# VestibularH1.net
KiCad netlist of a schematic drawn in EAGLE
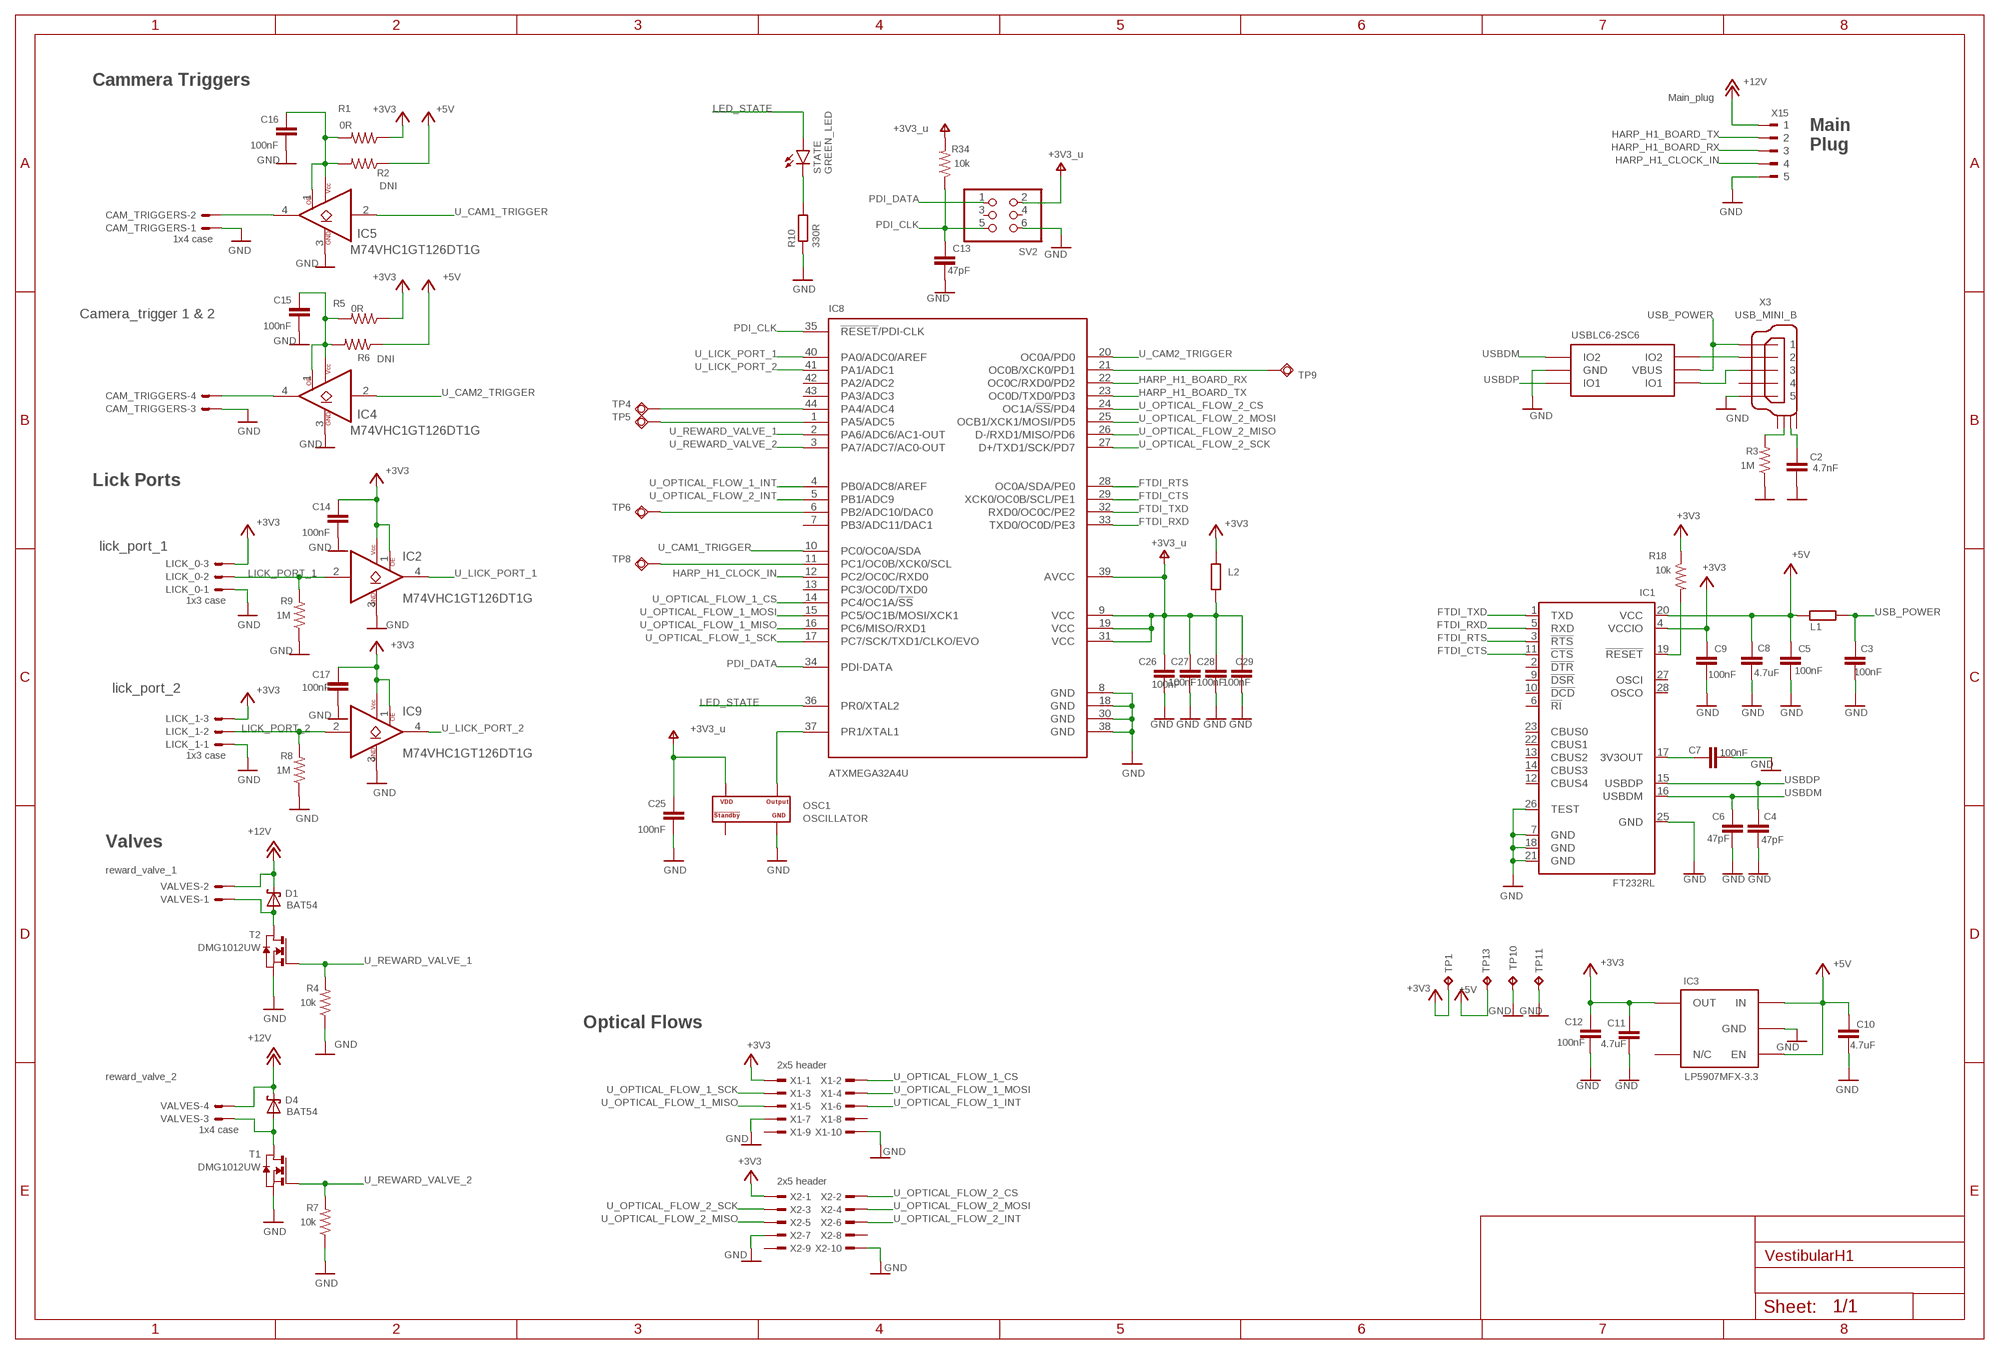
[diagram p0: schematic, sheet 1]

(export (version "E")
  (design (tool "Eeschema 10.0.6"))
  (components
    (comp (ref "C2")
      (value "4.7nF")
      (footprint "eagle-import:C0402K")
      (fields (field (name "MPN") "CC0402KRX7R8BB472"))
      (libsource (lib "eagle-import") (part "C-EUC0402K"))
    )
    (comp (ref "C3")
      (value "100nF")
      (footprint "eagle-import:C0402K")
      (fields (field (name "MPN") "C1005X7R1H104K050BB"))
      (libsource (lib "eagle-import") (part "C-EUC0402K"))
    )
    (comp (ref "C4")
      (value "47pF")
      (footprint "eagle-import:C0402K")
      (fields (field (name "MPN") "04025A470JAT2A"))
      (libsource (lib "eagle-import") (part "C-EUC0402K"))
    )
    (comp (ref "C5")
      (value "100nF")
      (footprint "eagle-import:C0402K")
      (fields (field (name "MPN") "C1005X7R1H104K050BB"))
      (libsource (lib "eagle-import") (part "C-EUC0402K"))
    )
    (comp (ref "C6")
      (value "47pF")
      (footprint "eagle-import:C0402K")
      (fields (field (name "MPN") "04025A470JAT2A"))
      (libsource (lib "eagle-import") (part "C-EUC0402K"))
    )
    (comp (ref "C7")
      (value "100nF")
      (footprint "eagle-import:C0402K")
      (fields (field (name "MPN") "C1005X7R1H104K050BB"))
      (libsource (lib "eagle-import") (part "C-EUC0402K"))
    )
    (comp (ref "C8")
      (value "4.7uF")
      (footprint "eagle-import:C0603")
      (fields (field (name "MPN") "C1608X6S1C475K080AC"))
      (libsource (lib "eagle-import") (part "C-EUC0603"))
    )
    (comp (ref "C9")
      (value "100nF")
      (footprint "eagle-import:C0402K")
      (fields (field (name "MPN") "C1005X7R1H104K050BB"))
      (libsource (lib "eagle-import") (part "C-EUC0402K"))
    )
    (comp (ref "C10")
      (value "4.7uF")
      (footprint "eagle-import:C0603")
      (fields (field (name "MPN") "C1608X6S1C475K080AC"))
      (libsource (lib "eagle-import") (part "C-EUC0603"))
    )
    (comp (ref "C11")
      (value "4.7uF")
      (footprint "eagle-import:C0603K")
      (fields (field (name "MPN") "C1608X6S1C475K080AC"))
      (libsource (lib "eagle-import") (part "C-EUC0603K"))
    )
    (comp (ref "C12")
      (value "100nF")
      (footprint "eagle-import:C0402K")
      (fields (field (name "MPN") "C1005X7R1H104K050BB"))
      (libsource (lib "eagle-import") (part "C-EUC0402K"))
    )
    (comp (ref "C13")
      (value "47pF")
      (footprint "eagle-import:C0402K")
      (fields (field (name "MPN") "04025A470JAT2A"))
      (libsource (lib "eagle-import") (part "C-EUC0402K"))
    )
    (comp (ref "C14")
      (value "100nF")
      (footprint "eagle-import:C0402K")
      (fields (field (name "MPN") "C1005X7R1H104K050BB"))
      (libsource (lib "eagle-import") (part "C-EUC0402K"))
    )
    (comp (ref "C15")
      (value "100nF")
      (footprint "eagle-import:C0402K")
      (fields (field (name "MPN") "C1005X7R1H104K050BB"))
      (libsource (lib "eagle-import") (part "C-EUC0402K"))
    )
    (comp (ref "C16")
      (value "100nF")
      (footprint "eagle-import:C0402K")
      (fields (field (name "MPN") "C1005X7R1H104K050BB"))
      (libsource (lib "eagle-import") (part "C-EUC0402K"))
    )
    (comp (ref "C17")
      (value "100nF")
      (footprint "eagle-import:C0402K")
      (fields (field (name "MPN") "C1005X7R1H104K050BB"))
      (libsource (lib "eagle-import") (part "C-EUC0402K"))
    )
    (comp (ref "C25")
      (value "100nF")
      (footprint "eagle-import:C0402K")
      (fields (field (name "MPN") "C1005X7R1H104K050BB"))
      (libsource (lib "eagle-import") (part "C-EUC0402K"))
    )
    (comp (ref "C26")
      (value "100nF")
      (footprint "eagle-import:C0402K")
      (fields (field (name "MPN") "C1005X7R1H104K050BB"))
      (libsource (lib "eagle-import") (part "C-EUC0402K"))
    )
    (comp (ref "C27")
      (value "100nF")
      (footprint "eagle-import:C0402K")
      (fields (field (name "MPN") "C1005X7R1H104K050BB"))
      (libsource (lib "eagle-import") (part "C-EUC0402K"))
    )
    (comp (ref "C28")
      (value "100nF")
      (footprint "eagle-import:C0402K")
      (fields (field (name "MPN") "C1005X7R1H104K050BB"))
      (libsource (lib "eagle-import") (part "C-EUC0402K"))
    )
    (comp (ref "C29")
      (value "100nF")
      (footprint "eagle-import:C0402K")
      (fields (field (name "MPN") "C1005X7R1H104K050BB"))
      (libsource (lib "eagle-import") (part "C-EUC0402K"))
    )
    (comp (ref "CAM_TRIGGERS")
      (value "1x4 case")
      (footprint "eagle-import:22-23-2041")
      (fields
        (field (name "MF") "MOLEX")
        (field (name "MPN") "22-23-2041")
        (field (name "MF_1") "-")
        (field (name "MPN_1") "282834-4")
        (field (name "OEPS") "OEPS070036")
      )
      (libsource (lib "eagle-import") (part "22-23-2041"))
    )
    (comp (ref "D1")
      (value "BAT54")
      (footprint "eagle-import:SOT23")
      (fields (field (name "MPN") "BAT54SLT1G"))
      (libsource (lib "eagle-import") (part "BAT54"))
    )
    (comp (ref "D4")
      (value "BAT54")
      (footprint "eagle-import:SOT23")
      (fields (field (name "MPN") "BAT54SLT1G"))
      (libsource (lib "eagle-import") (part "BAT54"))
    )
    (comp (ref "IC1")
      (value "FT232RL")
      (footprint "eagle-import:SSOP28")
      (libsource (lib "eagle-import") (part "FT232RL"))
    )
    (comp (ref "IC2")
      (value "M74VHC1GT126DT1G")
      (footprint "eagle-import:TSOP-5")
      (libsource (lib "eagle-import") (part "M74VHC1GT126DT1G"))
    )
    (comp (ref "IC3")
      (value "LP5907MFX-3.3")
      (footprint "eagle-import:TSOT23-5")
      (fields (field (name "MPN") "LP5907MFX-3.3/NOPB"))
      (libsource (lib "eagle-import") (part "TLV700XX"))
    )
    (comp (ref "IC4")
      (value "M74VHC1GT126DT1G")
      (footprint "eagle-import:TSOP-5")
      (libsource (lib "eagle-import") (part "M74VHC1GT126DT1G"))
    )
    (comp (ref "IC5")
      (value "M74VHC1GT126DT1G")
      (footprint "eagle-import:TSOP-5")
      (libsource (lib "eagle-import") (part "M74VHC1GT126DT1G"))
    )
    (comp (ref "IC7")
      (value "USBLC6-2SC6")
      (footprint "eagle-import:SOT23-6L")
      (libsource (lib "eagle-import") (part "USBLC6-2SC6"))
    )
    (comp (ref "IC8")
      (value "ATXMEGA32A4U")
      (footprint "eagle-import:TQFP44")
      (fields (field (name "MPN") "ATXMEGA32A4U-AUR"))
      (libsource (lib "eagle-import") (part "XMEGA-A4_AT-XMEGA-XXA4-AUTQFP44"))
    )
    (comp (ref "IC9")
      (value "M74VHC1GT126DT1G")
      (footprint "eagle-import:TSOP-5")
      (libsource (lib "eagle-import") (part "M74VHC1GT126DT1G"))
    )
    (comp (ref "L1")
      (value "40R@100MHz")
      (footprint "eagle-import:R0603")
      (fields (field (name "MPN") "MI0805K400R-10"))
      (libsource (lib "eagle-import") (part "R-EU_R0603"))
    )
    (comp (ref "L2")
      (value "40R@100MHz")
      (footprint "eagle-import:R0603")
      (fields (field (name "MPN") "MI0805K400R-10"))
      (libsource (lib "eagle-import") (part "R-EU_R0603"))
    )
    (comp (ref "LICK_0")
      (value "1x3 case")
      (footprint "eagle-import:22-23-2031")
      (fields
        (field (name "MF") "MOLEX")
        (field (name "MPN") "22-23-2031")
        (field (name "MF_1") "-")
        (field (name "MPN_1") "282834-3")
        (field (name "OEPS") "OEPS070035")
      )
      (libsource (lib "eagle-import") (part "22-23-2031"))
    )
    (comp (ref "LICK_1")
      (value "1x3 case")
      (footprint "eagle-import:22-23-2031")
      (fields
        (field (name "MF") "MOLEX")
        (field (name "MPN") "22-23-2031")
        (field (name "MF_1") "-")
        (field (name "MPN_1") "282834-3")
        (field (name "OEPS") "OEPS070035")
      )
      (libsource (lib "eagle-import") (part "22-23-2031"))
    )
    (comp (ref "OSC1")
      (value "OSCILLATOR")
      (footprint "eagle-import:OSCILLATOR_3.2X2.5")
      (fields (field (name "MPN") "DSC1001CI5-032.0000"))
      (libsource (lib "eagle-import") (part "OSCILLATOR"))
    )
    (comp (ref "R1")
      (value "0R")
      (footprint "eagle-import:R0402@1")
      (fields (field (name "MPN") "RC0402JR-070RL"))
      (libsource (lib "eagle-import") (part "R-US_R0402"))
    )
    (comp (ref "R2")
      (value "DNI")
      (footprint "eagle-import:R0402@1")
      (libsource (lib "eagle-import") (part "R-US_R0402"))
    )
    (comp (ref "R3")
      (value "1M")
      (footprint "eagle-import:R0402@1")
      (fields (field (name "MPN") "CRCW04021M00FKED"))
      (libsource (lib "eagle-import") (part "R-US_R0402"))
    )
    (comp (ref "R4")
      (value "10k")
      (footprint "eagle-import:R0402@1")
      (fields (field (name "MPN") "CRCW040210K0FKED"))
      (libsource (lib "eagle-import") (part "R-US_R0402"))
    )
    (comp (ref "R5")
      (value "0R")
      (footprint "eagle-import:R0402@1")
      (fields (field (name "MPN") "RC0402JR-070RL"))
      (libsource (lib "eagle-import") (part "R-US_R0402"))
    )
    (comp (ref "R6")
      (value "DNI")
      (footprint "eagle-import:R0402@1")
      (libsource (lib "eagle-import") (part "R-US_R0402"))
    )
    (comp (ref "R7")
      (value "10k")
      (footprint "eagle-import:R0402@1")
      (fields (field (name "MPN") "CRCW040210K0FKED"))
      (libsource (lib "eagle-import") (part "R-US_R0402"))
    )
    (comp (ref "R8")
      (value "1M")
      (footprint "eagle-import:R0402@1")
      (fields (field (name "MPN") "CRCW04021M00FKED"))
      (libsource (lib "eagle-import") (part "R-US_R0402"))
    )
    (comp (ref "R9")
      (value "1M")
      (footprint "eagle-import:R0402@1")
      (fields (field (name "MPN") "CRCW04021M00FKED"))
      (libsource (lib "eagle-import") (part "R-US_R0402"))
    )
    (comp (ref "R10")
      (value "330R")
      (footprint "eagle-import:R0402")
      (fields (field (name "MPN") "RC0402FR-07330RL"))
      (libsource (lib "eagle-import") (part "R-EU_R0402"))
    )
    (comp (ref "R18")
      (value "10k")
      (footprint "eagle-import:R0402@1")
      (fields (field (name "MPN") "CRCW040210K0FKED"))
      (libsource (lib "eagle-import") (part "R-US_R0402"))
    )
    (comp (ref "R34")
      (value "10k")
      (footprint "eagle-import:R0402@1")
      (fields (field (name "MPN") "CRCW040210K0FKED"))
      (libsource (lib "eagle-import") (part "R-US_R0402"))
    )
    (comp (ref "STATE")
      (value "GREEN_LED")
      (footprint "eagle-import:CHIP-LED0603")
      (fields (field (name "MPN") "LTST-C191KGKT"))
      (libsource (lib "eagle-import") (part "LEDCHIP-LED0603"))
    )
    (comp (ref "SV2")
      (value "PINHD-2X3")
      (footprint "eagle-import:2X03")
      (fields (field (name "MPN") "609-3210-ND"))
      (libsource (lib "eagle-import") (part "PINHD-2X3"))
    )
    (comp (ref "T1")
      (value "DMG1012UW")
      (footprint "eagle-import:SOT323")
      (fields (field (name "MPN") "DMG1012UW-7"))
      (libsource (lib "eagle-import") (part "DMG1012UW-7"))
    )
    (comp (ref "T2")
      (value "DMG1012UW")
      (footprint "eagle-import:SOT323")
      (fields (field (name "MPN") "DMG1012UW-7"))
      (libsource (lib "eagle-import") (part "DMG1012UW-7"))
    )
    (comp (ref "TP1")
      (value "NO_COMPONENT")
      (footprint "eagle-import:B1,27")
      (libsource (lib "eagle-import") (part "TPB1,27"))
    )
    (comp (ref "TP4")
      (value "NO_COMPONENT")
      (footprint "eagle-import:TP11R")
      (libsource (lib "eagle-import") (part "TPSQTP11R"))
    )
    (comp (ref "TP5")
      (value "NO_COMPONENT")
      (footprint "eagle-import:TP11R")
      (libsource (lib "eagle-import") (part "TPSQTP11R"))
    )
    (comp (ref "TP6")
      (value "NO_COMPONENT")
      (footprint "eagle-import:TP11R")
      (libsource (lib "eagle-import") (part "TPSQTP11R"))
    )
    (comp (ref "TP8")
      (value "NO_COMPONENT")
      (footprint "eagle-import:TP11R")
      (libsource (lib "eagle-import") (part "TPSQTP11R"))
    )
    (comp (ref "TP9")
      (value "NO_COMPONENT")
      (footprint "eagle-import:TP11R")
      (libsource (lib "eagle-import") (part "TPSQTP11R"))
    )
    (comp (ref "TP10")
      (value "NO_COMPONENT")
      (footprint "eagle-import:B1,27")
      (libsource (lib "eagle-import") (part "TPB1,27"))
    )
    (comp (ref "TP11")
      (value "NO_COMPONENT")
      (footprint "eagle-import:B1,27")
      (libsource (lib "eagle-import") (part "TPB1,27"))
    )
    (comp (ref "TP13")
      (value "NO_COMPONENT")
      (footprint "eagle-import:B1,27")
      (libsource (lib "eagle-import") (part "TPB1,27"))
    )
    (comp (ref "VALVES")
      (value "1x4 case")
      (footprint "eagle-import:22-23-2041")
      (fields
        (field (name "MF") "MOLEX")
        (field (name "MPN") "22-23-2041")
        (field (name "MF_1") "-")
        (field (name "MPN_1") "282834-4")
        (field (name "OEPS") "OEPS070036")
      )
      (libsource (lib "eagle-import") (part "22-23-2041"))
    )
    (comp (ref "X1")
      (value "2x5 header")
      (footprint "eagle-import:TSW-105-02-S-D")
      (fields (field (name "MPN") "2x5 header") (field (name "OEPS") "n.a."))
      (libsource (lib "eagle-import") (part "TSW-105-02-S-D"))
    )
    (comp (ref "X2")
      (value "2x5 header")
      (footprint "eagle-import:TSW-105-02-S-D")
      (fields (field (name "MPN") "2x5 header") (field (name "OEPS") "n.a."))
      (libsource (lib "eagle-import") (part "TSW-105-02-S-D"))
    )
    (comp (ref "X3")
      (value "USB_MINI_B")
      (footprint "eagle-import:240-0002-1")
      (fields (field (name "MPN") "UX60-MB-5S8"))
      (libsource (lib "eagle-import") (part "USB_MINI_B"))
    )
    (comp (ref "X15")
      (value "Main_plug")
      (footprint "eagle-import:90G-5")
      (fields (field (name "MPN") "20.155MH/5-E"))
      (libsource (lib "eagle-import") (part "90G-5"))
    )
  )
  (nets
    (net (code "1") (name "+3V3") (class "Default")
      (node (ref "C11") (pin "1") (pinfunction "1_1") (pintype "passive"))
      (node (ref "C12") (pin "1") (pinfunction "1_1") (pintype "passive"))
      (node (ref "C14") (pin "1") (pinfunction "1_1") (pintype "passive"))
      (node (ref "C17") (pin "1") (pinfunction "1_1") (pintype "passive"))
      (node (ref "C9") (pin "1") (pinfunction "1_1") (pintype "passive"))
      (node (ref "IC1") (pin "4") (pinfunction "VCCIO_4") (pintype "power_in"))
      (node (ref "IC2") (pin "1") (pinfunction "OE_1") (pintype "bidirectional"))
      (node (ref "IC2") (pin "5") (pinfunction "VCC_5") (pintype "bidirectional"))
      (node (ref "IC3") (pin "5") (pinfunction "OUT_5") (pintype "bidirectional"))
      (node (ref "IC9") (pin "1") (pinfunction "OE_1") (pintype "bidirectional"))
      (node (ref "IC9") (pin "5") (pinfunction "VCC_5") (pintype "bidirectional"))
      (node (ref "L2") (pin "2") (pinfunction "2_2") (pintype "passive"))
      (node (ref "LICK_0") (pin "3") (pinfunction "S_3") (pintype "passive"))
      (node (ref "LICK_1") (pin "3") (pinfunction "S_3") (pintype "passive"))
      (node (ref "R1") (pin "1") (pinfunction "1_1") (pintype "passive"))
      (node (ref "R18") (pin "1") (pinfunction "1_1") (pintype "passive"))
      (node (ref "R5") (pin "1") (pinfunction "1_1") (pintype "passive"))
      (node (ref "TP1") (pin "TP") (pinfunction "TP_TP") (pintype "input"))
      (node (ref "X1") (pin "1") (pinfunction "1_1") (pintype "passive"))
      (node (ref "X2") (pin "1") (pinfunction "1_1") (pintype "passive"))
    )
    (net (code "2") (name "+3V3_u") (class "Default")
      (node (ref "C25") (pin "1") (pinfunction "1_1") (pintype "passive"))
      (node (ref "C26") (pin "1") (pinfunction "1_1") (pintype "passive"))
      (node (ref "C27") (pin "1") (pinfunction "1_1") (pintype "passive"))
      (node (ref "C28") (pin "1") (pinfunction "1_1") (pintype "passive"))
      (node (ref "C29") (pin "1") (pinfunction "1_1") (pintype "passive"))
      (node (ref "IC8") (pin "19") (pinfunction "VCC_19") (pintype "power_in"))
      (node (ref "IC8") (pin "31") (pinfunction "VCC_31") (pintype "power_in"))
      (node (ref "IC8") (pin "39") (pinfunction "AVCC_39") (pintype "power_in"))
      (node (ref "IC8") (pin "9") (pinfunction "VCC_9") (pintype "power_in"))
      (node (ref "L2") (pin "1") (pinfunction "1_1") (pintype "passive"))
      (node (ref "OSC1") (pin "P$4") (pinfunction "VDD_P$4") (pintype "passive"))
      (node (ref "R34") (pin "2") (pinfunction "2_2") (pintype "passive"))
      (node (ref "SV2") (pin "2") (pinfunction "2_2") (pintype "passive"))
    )
    (net (code "3") (name "+5V") (class "Default")
      (node (ref "C10") (pin "1") (pinfunction "1_1") (pintype "passive"))
      (node (ref "C5") (pin "1") (pinfunction "1_1") (pintype "passive"))
      (node (ref "C8") (pin "1") (pinfunction "1_1") (pintype "passive"))
      (node (ref "IC1") (pin "20") (pinfunction "VCC_20") (pintype "power_in"))
      (node (ref "IC3") (pin "1") (pinfunction "IN_1") (pintype "bidirectional"))
      (node (ref "IC3") (pin "3") (pinfunction "EN_3") (pintype "bidirectional"))
      (node (ref "L1") (pin "1") (pinfunction "1_1") (pintype "passive"))
      (node (ref "R2") (pin "1") (pinfunction "1_1") (pintype "passive"))
      (node (ref "R6") (pin "1") (pinfunction "1_1") (pintype "passive"))
      (node (ref "TP13") (pin "TP") (pinfunction "TP_TP") (pintype "input"))
    )
    (net (code "4") (name "+12V") (class "Default")
      (node (ref "D1") (pin "3") (pinfunction "C_3") (pintype "passive"))
      (node (ref "D4") (pin "3") (pinfunction "C_3") (pintype "passive"))
      (node (ref "VALVES") (pin "2") (pinfunction "S_2") (pintype "passive"))
      (node (ref "VALVES") (pin "4") (pinfunction "S_4") (pintype "passive"))
      (node (ref "X15") (pin "1") (pinfunction "1_1") (pintype "passive"))
    )
    (net (code "5") (name "/FTDI_CTS") (class "Default")
      (node (ref "IC1") (pin "11") (pinfunction "~{CTS}_11") (pintype "input"))
      (node (ref "IC8") (pin "29") (pinfunction "XCK0/OC0B/SCL/PE1_29") (pintype "bidirectional"))
    )
    (net (code "6") (name "/FTDI_RTS") (class "Default")
      (node (ref "IC1") (pin "3") (pinfunction "~{RTS}_3") (pintype "output"))
      (node (ref "IC8") (pin "28") (pinfunction "OC0A/SDA/PE0_28") (pintype "bidirectional"))
    )
    (net (code "7") (name "/FTDI_RXD") (class "Default")
      (node (ref "IC1") (pin "5") (pinfunction "RXD_5") (pintype "input"))
      (node (ref "IC8") (pin "33") (pinfunction "TXD0/OC0D/PE3_33") (pintype "bidirectional"))
    )
    (net (code "8") (name "/FTDI_TXD") (class "Default")
      (node (ref "IC1") (pin "1") (pinfunction "TXD_1") (pintype "output"))
      (node (ref "IC8") (pin "32") (pinfunction "RXD0/OC0C/PE2_32") (pintype "bidirectional"))
    )
    (net (code "9") (name "/HARP_H1_BOARD_RX") (class "Default")
      (node (ref "IC8") (pin "22") (pinfunction "OC0C/RXD0/PD2_22") (pintype "bidirectional"))
      (node (ref "X15") (pin "3") (pinfunction "3_3") (pintype "passive"))
    )
    (net (code "10") (name "/HARP_H1_BOARD_TX") (class "Default")
      (node (ref "IC8") (pin "23") (pinfunction "OC0D/TXD0/PD3_23") (pintype "bidirectional"))
      (node (ref "X15") (pin "2") (pinfunction "2_2") (pintype "passive"))
    )
    (net (code "11") (name "/HARP_H1_CLOCK_IN") (class "Default")
      (node (ref "IC8") (pin "12") (pinfunction "PC2/OC0C/RXD0_12") (pintype "bidirectional"))
      (node (ref "X15") (pin "4") (pinfunction "4_4") (pintype "passive"))
    )
    (net (code "12") (name "/LED_STATE") (class "Default")
      (node (ref "IC8") (pin "36") (pinfunction "PR0/XTAL2_36") (pintype "bidirectional"))
      (node (ref "STATE") (pin "A") (pinfunction "A_A") (pintype "passive"))
    )
    (net (code "13") (name "/LICK_PORT_1") (class "Default")
      (node (ref "IC2") (pin "2") (pinfunction "A_2") (pintype "bidirectional"))
      (node (ref "LICK_0") (pin "2") (pinfunction "S_2") (pintype "passive"))
      (node (ref "R9") (pin "2") (pinfunction "2_2") (pintype "passive"))
    )
    (net (code "14") (name "/LICK_PORT_2") (class "Default")
      (node (ref "IC9") (pin "2") (pinfunction "A_2") (pintype "bidirectional"))
      (node (ref "LICK_1") (pin "2") (pinfunction "S_2") (pintype "passive"))
      (node (ref "R8") (pin "2") (pinfunction "2_2") (pintype "passive"))
    )
    (net (code "15") (name "/PDI_CLK") (class "Default")
      (node (ref "C13") (pin "1") (pinfunction "1_1") (pintype "passive"))
      (node (ref "IC8") (pin "35") (pinfunction "~{RESET}/PDI-CLK_35") (pintype "input"))
      (node (ref "R34") (pin "1") (pinfunction "1_1") (pintype "passive"))
      (node (ref "SV2") (pin "5") (pinfunction "5_5") (pintype "passive"))
    )
    (net (code "16") (name "/PDI_DATA") (class "Default")
      (node (ref "IC8") (pin "34") (pinfunction "PDI-DATA_34") (pintype "bidirectional"))
      (node (ref "SV2") (pin "1") (pinfunction "1_1") (pintype "passive"))
    )
    (net (code "17") (name "/USBDM") (class "Default")
      (node (ref "C6") (pin "1") (pinfunction "1_1") (pintype "passive"))
      (node (ref "IC1") (pin "16") (pinfunction "USBDM_16") (pintype "bidirectional"))
      (node (ref "IC7") (pin "P$3") (pinfunction "IO2_P$3") (pintype "bidirectional"))
    )
    (net (code "18") (name "/USBDP") (class "Default")
      (node (ref "C4") (pin "1") (pinfunction "1_1") (pintype "passive"))
      (node (ref "IC1") (pin "15") (pinfunction "USBDP_15") (pintype "bidirectional"))
      (node (ref "IC7") (pin "P$1") (pinfunction "IO1_P$1") (pintype "bidirectional"))
    )
    (net (code "19") (name "/USB_POWER") (class "Default")
      (node (ref "C3") (pin "1") (pinfunction "1_1") (pintype "passive"))
      (node (ref "IC7") (pin "P$5") (pinfunction "VBUS_P$5") (pintype "bidirectional"))
      (node (ref "L1") (pin "2") (pinfunction "2_2") (pintype "passive"))
      (node (ref "X3") (pin "P$1") (pinfunction "1_P$1") (pintype "bidirectional"))
    )
    (net (code "20") (name "/U_CAM1_TRIGGER") (class "Default")
      (node (ref "IC5") (pin "2") (pinfunction "A_2") (pintype "bidirectional"))
      (node (ref "IC8") (pin "10") (pinfunction "PC0/OC0A/SDA_10") (pintype "bidirectional"))
    )
    (net (code "21") (name "/U_CAM2_TRIGGER") (class "Default")
      (node (ref "IC4") (pin "2") (pinfunction "A_2") (pintype "bidirectional"))
      (node (ref "IC8") (pin "20") (pinfunction "OC0A/PD0_20") (pintype "bidirectional"))
    )
    (net (code "22") (name "/U_LICK_PORT_1") (class "Default")
      (node (ref "IC2") (pin "4") (pinfunction "Y_4") (pintype "bidirectional"))
      (node (ref "IC8") (pin "40") (pinfunction "PA0/ADC0/AREF_40") (pintype "bidirectional"))
    )
    (net (code "23") (name "/U_LICK_PORT_2") (class "Default")
      (node (ref "IC8") (pin "41") (pinfunction "PA1/ADC1_41") (pintype "bidirectional"))
      (node (ref "IC9") (pin "4") (pinfunction "Y_4") (pintype "bidirectional"))
    )
    (net (code "24") (name "/U_OPTICAL_FLOW_1_CS") (class "Default")
      (node (ref "IC8") (pin "14") (pinfunction "PC4/OC1A/~{SS}_14") (pintype "bidirectional"))
      (node (ref "X1") (pin "2") (pinfunction "1_2") (pintype "passive"))
    )
    (net (code "25") (name "/U_OPTICAL_FLOW_1_INT") (class "Default")
      (node (ref "IC8") (pin "4") (pinfunction "PB0/ADC8/AREF_4") (pintype "bidirectional"))
      (node (ref "X1") (pin "6") (pinfunction "1_6") (pintype "passive"))
    )
    (net (code "26") (name "/U_OPTICAL_FLOW_1_MISO") (class "Default")
      (node (ref "IC8") (pin "16") (pinfunction "PC6/MISO/RXD1_16") (pintype "bidirectional"))
      (node (ref "X1") (pin "5") (pinfunction "1_5") (pintype "passive"))
    )
    (net (code "27") (name "/U_OPTICAL_FLOW_1_MOSI") (class "Default")
      (node (ref "IC8") (pin "15") (pinfunction "PC5/OC1B/MOSI/XCK1_15") (pintype "bidirectional"))
      (node (ref "X1") (pin "4") (pinfunction "1_4") (pintype "passive"))
    )
    (net (code "28") (name "/U_OPTICAL_FLOW_1_SCK") (class "Default")
      (node (ref "IC8") (pin "17") (pinfunction "PC7/SCK/TXD1/CLKO/EVO_17") (pintype "bidirectional"))
      (node (ref "X1") (pin "3") (pinfunction "1_3") (pintype "passive"))
    )
    (net (code "29") (name "/U_OPTICAL_FLOW_2_CS") (class "Default")
      (node (ref "IC8") (pin "24") (pinfunction "OC1A/~{SS}/PD4_24") (pintype "bidirectional"))
      (node (ref "X2") (pin "2") (pinfunction "1_2") (pintype "passive"))
    )
    (net (code "30") (name "/U_OPTICAL_FLOW_2_INT") (class "Default")
      (node (ref "IC8") (pin "5") (pinfunction "PB1/ADC9_5") (pintype "bidirectional"))
      (node (ref "X2") (pin "6") (pinfunction "1_6") (pintype "passive"))
    )
    (net (code "31") (name "/U_OPTICAL_FLOW_2_MISO") (class "Default")
      (node (ref "IC8") (pin "26") (pinfunction "D-/RXD1/MISO/PD6_26") (pintype "bidirectional"))
      (node (ref "X2") (pin "5") (pinfunction "1_5") (pintype "passive"))
    )
    (net (code "32") (name "/U_OPTICAL_FLOW_2_MOSI") (class "Default")
      (node (ref "IC8") (pin "25") (pinfunction "OCB1/XCK1/MOSI/PD5_25") (pintype "bidirectional"))
      (node (ref "X2") (pin "4") (pinfunction "1_4") (pintype "passive"))
    )
    (net (code "33") (name "/U_OPTICAL_FLOW_2_SCK") (class "Default")
      (node (ref "IC8") (pin "27") (pinfunction "D+/TXD1/SCK/PD7_27") (pintype "bidirectional"))
      (node (ref "X2") (pin "3") (pinfunction "1_3") (pintype "passive"))
    )
    (net (code "34") (name "/U_REWARD_VALVE_1") (class "Default")
      (node (ref "IC8") (pin "2") (pinfunction "PA6/ADC6/AC1-OUT_2") (pintype "bidirectional"))
      (node (ref "R4") (pin "2") (pinfunction "2_2") (pintype "passive"))
      (node (ref "T2") (pin "1") (pinfunction "G_1") (pintype "passive"))
    )
    (net (code "35") (name "/U_REWARD_VALVE_2") (class "Default")
      (node (ref "IC8") (pin "3") (pinfunction "PA7/ADC7/AC0-OUT_3") (pintype "bidirectional"))
      (node (ref "R7") (pin "2") (pinfunction "2_2") (pintype "passive"))
      (node (ref "T1") (pin "1") (pinfunction "G_1") (pintype "passive"))
    )
    (net (code "36") (name "GND") (class "Default")
      (node (ref "C10") (pin "2") (pinfunction "2_2") (pintype "passive"))
      (node (ref "C11") (pin "2") (pinfunction "2_2") (pintype "passive"))
      (node (ref "C12") (pin "2") (pinfunction "2_2") (pintype "passive"))
      (node (ref "C13") (pin "2") (pinfunction "2_2") (pintype "passive"))
      (node (ref "C14") (pin "2") (pinfunction "2_2") (pintype "passive"))
      (node (ref "C15") (pin "2") (pinfunction "2_2") (pintype "passive"))
      (node (ref "C16") (pin "2") (pinfunction "2_2") (pintype "passive"))
      (node (ref "C17") (pin "2") (pinfunction "2_2") (pintype "passive"))
      (node (ref "C2") (pin "2") (pinfunction "2_2") (pintype "passive"))
      (node (ref "C25") (pin "2") (pinfunction "2_2") (pintype "passive"))
      (node (ref "C26") (pin "2") (pinfunction "2_2") (pintype "passive"))
      (node (ref "C27") (pin "2") (pinfunction "2_2") (pintype "passive"))
      (node (ref "C28") (pin "2") (pinfunction "2_2") (pintype "passive"))
      (node (ref "C29") (pin "2") (pinfunction "2_2") (pintype "passive"))
      (node (ref "C3") (pin "2") (pinfunction "2_2") (pintype "passive"))
      (node (ref "C4") (pin "2") (pinfunction "2_2") (pintype "passive"))
      (node (ref "C5") (pin "2") (pinfunction "2_2") (pintype "passive"))
      (node (ref "C6") (pin "2") (pinfunction "2_2") (pintype "passive"))
      (node (ref "C7") (pin "2") (pinfunction "2_2") (pintype "passive"))
      (node (ref "C8") (pin "2") (pinfunction "2_2") (pintype "passive"))
      (node (ref "C9") (pin "2") (pinfunction "2_2") (pintype "passive"))
      (node (ref "CAM_TRIGGERS") (pin "1") (pinfunction "S_1") (pintype "passive"))
      (node (ref "CAM_TRIGGERS") (pin "3") (pinfunction "S_3") (pintype "passive"))
      (node (ref "IC1") (pin "18") (pinfunction "GND_18") (pintype "power_in"))
      (node (ref "IC1") (pin "21") (pinfunction "GND_21") (pintype "power_in"))
      (node (ref "IC1") (pin "25") (pinfunction "GND_25") (pintype "power_in"))
      (node (ref "IC1") (pin "26") (pinfunction "TEST_26") (pintype "input"))
      (node (ref "IC1") (pin "7") (pinfunction "GND_7") (pintype "power_in"))
      (node (ref "IC2") (pin "3") (pinfunction "GND_3") (pintype "bidirectional"))
      (node (ref "IC3") (pin "2") (pinfunction "GND_2") (pintype "bidirectional"))
      (node (ref "IC4") (pin "3") (pinfunction "GND_3") (pintype "bidirectional"))
      (node (ref "IC5") (pin "3") (pinfunction "GND_3") (pintype "bidirectional"))
      (node (ref "IC7") (pin "P$2") (pinfunction "GND_P$2") (pintype "bidirectional"))
      (node (ref "IC8") (pin "18") (pinfunction "GND_18") (pintype "power_in"))
      (node (ref "IC8") (pin "30") (pinfunction "GND_30") (pintype "power_in"))
      (node (ref "IC8") (pin "38") (pinfunction "GND_38") (pintype "power_in"))
      (node (ref "IC8") (pin "8") (pinfunction "GND_8") (pintype "power_in"))
      (node (ref "IC9") (pin "3") (pinfunction "GND_3") (pintype "bidirectional"))
      (node (ref "LICK_0") (pin "1") (pinfunction "S_1") (pintype "passive"))
      (node (ref "LICK_1") (pin "1") (pinfunction "S_1") (pintype "passive"))
      (node (ref "OSC1") (pin "P$2") (pinfunction "GND_P$2") (pintype "passive"))
      (node (ref "R10") (pin "1") (pinfunction "1_1") (pintype "passive"))
      (node (ref "R3") (pin "1") (pinfunction "1_1") (pintype "passive"))
      (node (ref "R4") (pin "1") (pinfunction "1_1") (pintype "passive"))
      (node (ref "R7") (pin "1") (pinfunction "1_1") (pintype "passive"))
      (node (ref "R8") (pin "1") (pinfunction "1_1") (pintype "passive"))
      (node (ref "R9") (pin "1") (pinfunction "1_1") (pintype "passive"))
      (node (ref "SV2") (pin "6") (pinfunction "6_6") (pintype "passive"))
      (node (ref "T1") (pin "2") (pinfunction "S_2") (pintype "passive"))
      (node (ref "T2") (pin "2") (pinfunction "S_2") (pintype "passive"))
      (node (ref "TP10") (pin "TP") (pinfunction "TP_TP") (pintype "input"))
      (node (ref "TP11") (pin "TP") (pinfunction "TP_TP") (pintype "input"))
      (node (ref "X1") (pin "10") (pinfunction "1_10") (pintype "passive"))
      (node (ref "X1") (pin "7") (pinfunction "1_7") (pintype "passive"))
      (node (ref "X15") (pin "5") (pinfunction "5_5") (pintype "passive"))
      (node (ref "X2") (pin "10") (pinfunction "1_10") (pintype "passive"))
      (node (ref "X2") (pin "7") (pinfunction "1_7") (pintype "passive"))
      (node (ref "X3") (pin "P$5") (pinfunction "5_P$5") (pintype "bidirectional"))
    )
    (net (code "37") (name "Net-(CAM_TRIGGERSB-S)") (class "Default")
      (node (ref "CAM_TRIGGERS") (pin "2") (pinfunction "S_2") (pintype "passive"))
      (node (ref "IC5") (pin "4") (pinfunction "Y_4") (pintype "bidirectional"))
    )
    (net (code "38") (name "Net-(CAM_TRIGGERSD-S)") (class "Default")
      (node (ref "CAM_TRIGGERS") (pin "4") (pinfunction "S_4") (pintype "passive"))
      (node (ref "IC4") (pin "4") (pinfunction "Y_4") (pintype "bidirectional"))
    )
    (net (code "39") (name "Net-(D1-A)") (class "Default")
      (node (ref "D1") (pin "1") (pinfunction "A_1") (pintype "passive"))
      (node (ref "T2") (pin "3") (pinfunction "D_3") (pintype "passive"))
      (node (ref "VALVES") (pin "1") (pinfunction "S_1") (pintype "passive"))
    )
    (net (code "40") (name "Net-(D4-A)") (class "Default")
      (node (ref "D4") (pin "1") (pinfunction "A_1") (pintype "passive"))
      (node (ref "T1") (pin "3") (pinfunction "D_3") (pintype "passive"))
      (node (ref "VALVES") (pin "3") (pinfunction "S_3") (pintype "passive"))
    )
    (net (code "41") (name "Net-(IC1-3V3OUT)") (class "Default")
      (node (ref "C7") (pin "1") (pinfunction "1_1") (pintype "passive"))
      (node (ref "IC1") (pin "17") (pinfunction "3V3OUT_17") (pintype "output"))
    )
    (net (code "42") (name "Net-(IC1-~{RESET})") (class "Default")
      (node (ref "IC1") (pin "19") (pinfunction "~{RESET}_19") (pintype "input"))
      (node (ref "R18") (pin "2") (pinfunction "2_2") (pintype "passive"))
    )
    (net (code "43") (name "Net-(IC4-OE)") (class "Default")
      (node (ref "C15") (pin "1") (pinfunction "1_1") (pintype "passive"))
      (node (ref "IC4") (pin "1") (pinfunction "OE_1") (pintype "bidirectional"))
      (node (ref "IC4") (pin "5") (pinfunction "VCC_5") (pintype "bidirectional"))
      (node (ref "R5") (pin "2") (pinfunction "2_2") (pintype "passive"))
      (node (ref "R6") (pin "2") (pinfunction "2_2") (pintype "passive"))
    )
    (net (code "44") (name "Net-(IC5-OE)") (class "Default")
      (node (ref "C16") (pin "1") (pinfunction "1_1") (pintype "passive"))
      (node (ref "IC5") (pin "1") (pinfunction "OE_1") (pintype "bidirectional"))
      (node (ref "IC5") (pin "5") (pinfunction "VCC_5") (pintype "bidirectional"))
      (node (ref "R1") (pin "2") (pinfunction "2_2") (pintype "passive"))
      (node (ref "R2") (pin "2") (pinfunction "2_2") (pintype "passive"))
    )
    (net (code "45") (name "Net-(IC8-OC0B{slash}XCK0{slash}PD1)") (class "Default")
      (node (ref "IC8") (pin "21") (pinfunction "OC0B/XCK0/PD1_21") (pintype "bidirectional"))
      (node (ref "TP9") (pin "TP") (pinfunction "TP_TP") (pintype "input"))
    )
    (net (code "46") (name "Net-(IC8-PA4{slash}ADC4)") (class "Default")
      (node (ref "IC8") (pin "44") (pinfunction "PA4/ADC4_44") (pintype "bidirectional"))
      (node (ref "TP4") (pin "TP") (pinfunction "TP_TP") (pintype "input"))
    )
    (net (code "47") (name "Net-(IC8-PA5{slash}ADC5)") (class "Default")
      (node (ref "IC8") (pin "1") (pinfunction "PA5/ADC5_1") (pintype "bidirectional"))
      (node (ref "TP5") (pin "TP") (pinfunction "TP_TP") (pintype "input"))
    )
    (net (code "48") (name "Net-(IC8-PB2{slash}ADC10{slash}DAC0)") (class "Default")
      (node (ref "IC8") (pin "6") (pinfunction "PB2/ADC10/DAC0_6") (pintype "bidirectional"))
      (node (ref "TP6") (pin "TP") (pinfunction "TP_TP") (pintype "input"))
    )
    (net (code "49") (name "Net-(IC8-PC1{slash}OC0B{slash}XCK0{slash}SCL)") (class "Default")
      (node (ref "IC8") (pin "11") (pinfunction "PC1/OC0B/XCK0/SCL_11") (pintype "bidirectional"))
      (node (ref "TP8") (pin "TP") (pinfunction "TP_TP") (pintype "input"))
    )
    (net (code "50") (name "Net-(IC8-PR1{slash}XTAL1)") (class "Default")
      (node (ref "IC8") (pin "37") (pinfunction "PR1/XTAL1_37") (pintype "bidirectional"))
      (node (ref "OSC1") (pin "P$3") (pinfunction "OUTPUT_P$3") (pintype "passive"))
    )
    (net (code "51") (name "Net-(R10-Pad2)") (class "Default")
      (node (ref "R10") (pin "2") (pinfunction "2_2") (pintype "passive"))
      (node (ref "STATE") (pin "C") (pinfunction "C_C") (pintype "passive"))
    )
    (net (code "52") (name "Net-(X3-2)") (class "Default")
      (node (ref "IC7") (pin "P$4") (pinfunction "IO2_P$4") (pintype "bidirectional"))
      (node (ref "X3") (pin "P$2") (pinfunction "2_P$2") (pintype "bidirectional"))
    )
    (net (code "53") (name "Net-(X3-3)") (class "Default")
      (node (ref "IC7") (pin "P$6") (pinfunction "IO1_P$6") (pintype "bidirectional"))
      (node (ref "X3") (pin "P$3") (pinfunction "3_P$3") (pintype "bidirectional"))
    )
    (net (code "54") (name "Net-(X3-P$2)") (class "Default")
      (node (ref "R3") (pin "2") (pinfunction "2_2") (pintype "passive"))
      (node (ref "X3") (pin "SHIELD_2") (pinfunction "P$2_SHIELD_2") (pintype "bidirectional"))
    )
    (net (code "55") (name "Net-(X3-P$3)") (class "Default")
      (node (ref "C2") (pin "1") (pinfunction "1_1") (pintype "passive"))
      (node (ref "X3") (pin "SHIELD_3") (pinfunction "P$3_SHIELD_3") (pintype "bidirectional"))
    )
    (net (code "56") (name "unconnected-(IC1-CBUS0-Pad23)") (class "Default")
      (node (ref "IC1") (pin "23") (pinfunction "CBUS0_23") (pintype "bidirectional"))
    )
    (net (code "57") (name "unconnected-(IC1-CBUS1-Pad22)") (class "Default")
      (node (ref "IC1") (pin "22") (pinfunction "CBUS1_22") (pintype "bidirectional"))
    )
    (net (code "58") (name "unconnected-(IC1-CBUS2-Pad13)") (class "Default")
      (node (ref "IC1") (pin "13") (pinfunction "CBUS2_13") (pintype "bidirectional"))
    )
    (net (code "59") (name "unconnected-(IC1-CBUS3-Pad14)") (class "Default")
      (node (ref "IC1") (pin "14") (pinfunction "CBUS3_14") (pintype "bidirectional"))
    )
    (net (code "60") (name "unconnected-(IC1-CBUS4-Pad12)") (class "Default")
      (node (ref "IC1") (pin "12") (pinfunction "CBUS4_12") (pintype "bidirectional"))
    )
    (net (code "61") (name "unconnected-(IC1-OSCI-Pad27)") (class "Default")
      (node (ref "IC1") (pin "27") (pinfunction "OSCI_27") (pintype "input"))
    )
    (net (code "62") (name "unconnected-(IC1-OSCO-Pad28)") (class "Default")
      (node (ref "IC1") (pin "28") (pinfunction "OSCO_28") (pintype "output"))
    )
    (net (code "63") (name "unconnected-(IC1-~{DCD}-Pad10)") (class "Default")
      (node (ref "IC1") (pin "10") (pinfunction "~{DCD}_10") (pintype "input"))
    )
    (net (code "64") (name "unconnected-(IC1-~{DSR}-Pad9)") (class "Default")
      (node (ref "IC1") (pin "9") (pinfunction "~{DSR}_9") (pintype "input"))
    )
    (net (code "65") (name "unconnected-(IC1-~{DTR}-Pad2)") (class "Default")
      (node (ref "IC1") (pin "2") (pinfunction "~{DTR}_2") (pintype "output"))
    )
    (net (code "66") (name "unconnected-(IC1-~{RI}-Pad6)") (class "Default")
      (node (ref "IC1") (pin "6") (pinfunction "~{RI}_6") (pintype "input"))
    )
    (net (code "67") (name "unconnected-(IC3-N{slash}C-Pad4)") (class "Default")
      (node (ref "IC3") (pin "4") (pinfunction "N/C_4") (pintype "bidirectional"))
    )
    (net (code "68") (name "unconnected-(IC8-PA2{slash}ADC2-Pad42)") (class "Default")
      (node (ref "IC8") (pin "42") (pinfunction "PA2/ADC2_42") (pintype "bidirectional"))
    )
    (net (code "69") (name "unconnected-(IC8-PA3{slash}ADC3-Pad43)") (class "Default")
      (node (ref "IC8") (pin "43") (pinfunction "PA3/ADC3_43") (pintype "bidirectional"))
    )
    (net (code "70") (name "unconnected-(IC8-PB3{slash}ADC11{slash}DAC1-Pad7)") (class "Default")
      (node (ref "IC8") (pin "7") (pinfunction "PB3/ADC11/DAC1_7") (pintype "bidirectional"))
    )
    (net (code "71") (name "unconnected-(IC8-PC3{slash}OC0D{slash}TXD0-Pad13)") (class "Default")
      (node (ref "IC8") (pin "13") (pinfunction "PC3/OC0D/TXD0_13") (pintype "bidirectional"))
    )
    (net (code "72") (name "unconnected-(OSC1-STANDBY#-PadP$1)") (class "Default")
      (node (ref "OSC1") (pin "P$1") (pinfunction "STANDBY#_P$1") (pintype "passive"))
    )
    (net (code "73") (name "unconnected-(SV2-Pad3)") (class "Default")
      (node (ref "SV2") (pin "3") (pinfunction "3_3") (pintype "passive"))
    )
    (net (code "74") (name "unconnected-(SV2-Pad4)") (class "Default")
      (node (ref "SV2") (pin "4") (pinfunction "4_4") (pintype "passive"))
    )
    (net (code "75") (name "unconnected-(X1I-1-Pad8)") (class "Default")
      (node (ref "X1") (pin "8") (pinfunction "1_8") (pintype "passive"))
    )
    (net (code "76") (name "unconnected-(X1J-1-Pad9)") (class "Default")
      (node (ref "X1") (pin "9") (pinfunction "1_9") (pintype "passive"))
    )
    (net (code "77") (name "unconnected-(X2I-1-Pad8)") (class "Default")
      (node (ref "X2") (pin "8") (pinfunction "1_8") (pintype "passive"))
    )
    (net (code "78") (name "unconnected-(X2J-1-Pad9)") (class "Default")
      (node (ref "X2") (pin "9") (pinfunction "1_9") (pintype "passive"))
    )
    (net (code "79") (name "unconnected-(X3-4-PadP$4)") (class "Default")
      (node (ref "X3") (pin "P$4") (pinfunction "4_P$4") (pintype "bidirectional"))
    )
    (net (code "80") (name "unconnected-(X3-P$1-PadSHIELD_1)") (class "Default")
      (node (ref "X3") (pin "SHIELD_1") (pinfunction "P$1_SHIELD_1") (pintype "bidirectional"))
    )
    (net (code "81") (name "unconnected-(X3-P$4-PadSHIELD_4)") (class "Default")
      (node (ref "X3") (pin "SHIELD_4") (pinfunction "P$4_SHIELD_4") (pintype "bidirectional"))
    )
  )
)
